# H-brigde_connector.net
KiCad netlist of a schematic drawn in Altium Designer
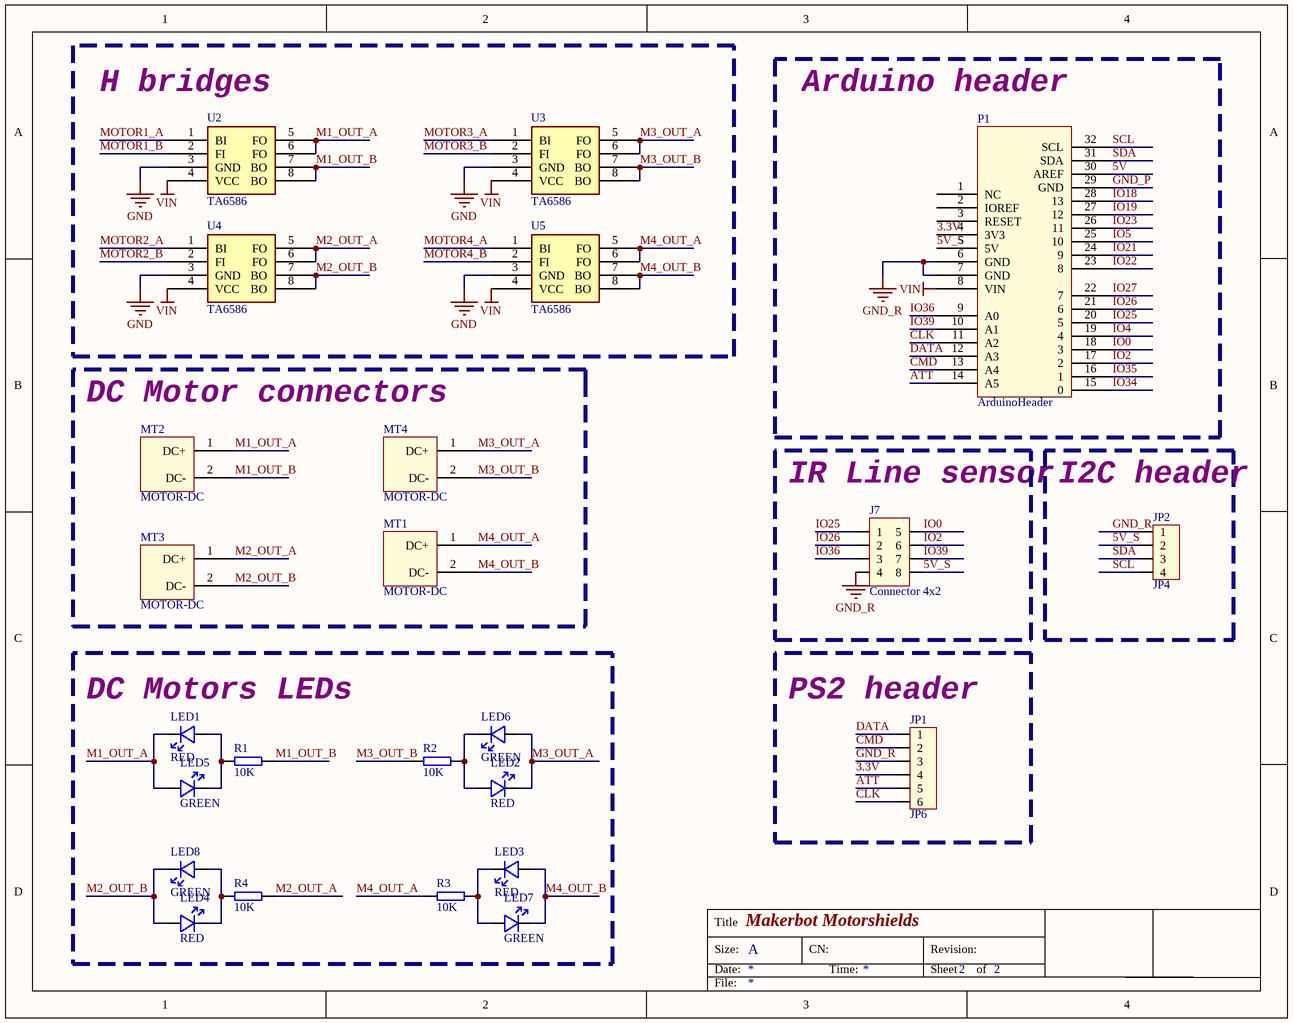
[diagram p0: H-brigde_connector.SchDoc]

(export (version "E")
  (design (tool "Eeschema 10.0.6"))
  (components
    (comp (ref "J7")
      (value "Connector 4x2")
      (footprint "JP4x2")
      (libsource (lib "My library altium") (part "JP4x2"))
    )
    (comp (ref "JP1")
      (value "JP6")
      (footprint "CON6")
      (description "Connector 6")
      (libsource (lib "My Library") (part "Con6"))
    )
    (comp (ref "JP2")
      (value "JP4")
      (footprint "CONN-TH_XH2.54-4AW")
      (description "Connector 4")
      (libsource (lib "My Library") (part "Con4"))
    )
    (comp (ref "LED1")
      (value "RED")
      (footprint "SMT0603P")
      (description "LED SM 0603 RED 1V95 FWD VOLTAGE")
      (libsource (lib "electronpowered") (part "LNJ237W82RA"))
    )
    (comp (ref "LED2")
      (value "RED")
      (footprint "SMT0603P")
      (description "LED SM 0603 RED 1V95 FWD VOLTAGE")
      (libsource (lib "electronpowered") (part "LNJ237W82RA"))
    )
    (comp (ref "LED3")
      (value "RED")
      (footprint "SMT0603P")
      (description "LED SM 0603 RED 1V95 FWD VOLTAGE")
      (libsource (lib "electronpowered") (part "LNJ237W82RA"))
    )
    (comp (ref "LED4")
      (value "RED")
      (footprint "SMT0603P")
      (description "LED SM 0603 RED 1V95 FWD VOLTAGE")
      (libsource (lib "electronpowered") (part "LNJ237W82RA"))
    )
    (comp (ref "LED5")
      (value "GREEN")
      (footprint "SMT0603P")
      (description "LED SM 0603 GREEN 1V95 FWD VOLTAGE")
      (libsource (lib "electronpowered") (part "LNJ337W83RA"))
    )
    (comp (ref "LED6")
      (value "GREEN")
      (footprint "SMT0603P")
      (description "LED SM 0603 GREEN 1V95 FWD VOLTAGE")
      (libsource (lib "electronpowered") (part "LNJ337W83RA"))
    )
    (comp (ref "LED7")
      (value "GREEN")
      (footprint "SMT0603P")
      (description "LED SM 0603 GREEN 1V95 FWD VOLTAGE")
      (libsource (lib "electronpowered") (part "LNJ337W83RA"))
    )
    (comp (ref "LED8")
      (value "GREEN")
      (footprint "SMT0603P")
      (description "LED SM 0603 GREEN 1V95 FWD VOLTAGE")
      (libsource (lib "electronpowered") (part "LNJ337W83RA"))
    )
    (comp (ref "MT1")
      (value "MOTOR-DC")
      (footprint "CON2-5.08DC")
      (libsource (lib "RASHBERRY_EXTERN") (part "MOTOR-DC"))
    )
    (comp (ref "MT2")
      (value "MOTOR-DC")
      (footprint "CON2-5.08DC")
      (libsource (lib "RASHBERRY_EXTERN") (part "MOTOR-DC"))
    )
    (comp (ref "MT3")
      (value "MOTOR-DC")
      (footprint "CON2-5.08DC")
      (libsource (lib "RASHBERRY_EXTERN") (part "MOTOR-DC"))
    )
    (comp (ref "MT4")
      (value "MOTOR-DC")
      (footprint "CON2-5.08DC")
      (libsource (lib "RASHBERRY_EXTERN") (part "MOTOR-DC"))
    )
    (comp (ref "P1")
      (value "ArduinoHeader")
      (footprint "ArduinoClone2")
      (libsource (lib "electronpowered") (part "ArduinoHeader"))
    )
    (comp (ref "R1")
      (value "10K")
      (footprint "SMT0603")
      (description "RES SM 0603 10K")
      (fields (field (name "Comment") "Resistor"))
      (libsource (lib "electronpowered") (part "RES-SM-0603-10K"))
    )
    (comp (ref "R2")
      (value "10K")
      (footprint "SMT0603")
      (description "RES SM 0603 10K")
      (fields (field (name "Comment") "Resistor"))
      (libsource (lib "electronpowered") (part "RES-SM-0603-10K"))
    )
    (comp (ref "R3")
      (value "10K")
      (footprint "SMT0603")
      (description "RES SM 0603 10K")
      (fields (field (name "Comment") "Resistor"))
      (libsource (lib "electronpowered") (part "RES-SM-0603-10K"))
    )
    (comp (ref "R4")
      (value "10K")
      (footprint "SMT0603")
      (description "RES SM 0603 10K")
      (fields (field (name "Comment") "Resistor"))
      (libsource (lib "electronpowered") (part "RES-SM-0603-10K"))
    )
    (comp (ref "U2")
      (value "TA6586")
      (footprint "DIP.100/8/W.300/L.400")
      (libsource (lib "TA6586") (part "TA6586"))
    )
    (comp (ref "U3")
      (value "TA6586")
      (footprint "DIP.100/8/W.300/L.400")
      (libsource (lib "TA6586") (part "TA6586"))
    )
    (comp (ref "U4")
      (value "TA6586")
      (footprint "DIP.100/8/W.300/L.400")
      (libsource (lib "TA6586") (part "TA6586"))
    )
    (comp (ref "U5")
      (value "TA6586")
      (footprint "DIP.100/8/W.300/L.400")
      (libsource (lib "TA6586") (part "TA6586"))
    )
  )
  (nets
    (net (code "1") (name "/3.3V") (class "Default")
      (node (ref "JP1") (pin "4") (pinfunction "4_4") (pintype "passive"))
      (node (ref "P1") (pin "4") (pinfunction "3V3_4") (pintype "passive"))
    )
    (net (code "2") (name "/5V") (class "Default")
      (node (ref "P1") (pin "30") (pinfunction "AREF_30") (pintype "passive"))
    )
    (net (code "3") (name "/5V_S") (class "Default")
      (node (ref "J7") (pin "8") (pinfunction "8_8") (pintype "passive"))
      (node (ref "JP2") (pin "2") (pinfunction "2_2") (pintype "passive"))
      (node (ref "P1") (pin "5") (pinfunction "5V_5") (pintype "passive"))
    )
    (net (code "4") (name "/ATT") (class "Default")
      (node (ref "JP1") (pin "5") (pinfunction "5_5") (pintype "passive"))
      (node (ref "P1") (pin "14") (pinfunction "A5_14") (pintype "passive"))
    )
    (net (code "5") (name "/CLK") (class "Default")
      (node (ref "JP1") (pin "6") (pinfunction "6_6") (pintype "passive"))
      (node (ref "P1") (pin "11") (pinfunction "A2_11") (pintype "passive"))
    )
    (net (code "6") (name "/CMD") (class "Default")
      (node (ref "JP1") (pin "2") (pinfunction "2_2") (pintype "passive"))
      (node (ref "P1") (pin "13") (pinfunction "A4_13") (pintype "passive"))
    )
    (net (code "7") (name "/DATA") (class "Default")
      (node (ref "JP1") (pin "1") (pinfunction "1_1") (pintype "passive"))
      (node (ref "P1") (pin "12") (pinfunction "A3_12") (pintype "passive"))
    )
    (net (code "8") (name "/GND_P") (class "Default")
      (node (ref "P1") (pin "29") (pinfunction "GND_29") (pintype "passive"))
    )
    (net (code "9") (name "/IO0") (class "Default")
      (node (ref "J7") (pin "5") (pinfunction "5_5") (pintype "passive"))
      (node (ref "P1") (pin "18") (pinfunction "3_18") (pintype "passive"))
    )
    (net (code "10") (name "/IO2") (class "Default")
      (node (ref "J7") (pin "6") (pinfunction "6_6") (pintype "passive"))
      (node (ref "P1") (pin "17") (pinfunction "2_17") (pintype "passive"))
    )
    (net (code "11") (name "/IO4") (class "Default")
      (node (ref "P1") (pin "19") (pinfunction "4_19") (pintype "passive"))
    )
    (net (code "12") (name "/IO5") (class "Default")
      (node (ref "P1") (pin "25") (pinfunction "10_25") (pintype "passive"))
    )
    (net (code "13") (name "/IO18") (class "Default")
      (node (ref "P1") (pin "28") (pinfunction "13_28") (pintype "passive"))
    )
    (net (code "14") (name "/IO19") (class "Default")
      (node (ref "P1") (pin "27") (pinfunction "12_27") (pintype "passive"))
    )
    (net (code "15") (name "/IO21") (class "Default")
      (node (ref "P1") (pin "24") (pinfunction "9_24") (pintype "passive"))
    )
    (net (code "16") (name "/IO22") (class "Default")
      (node (ref "P1") (pin "23") (pinfunction "8_23") (pintype "passive"))
    )
    (net (code "17") (name "/IO23") (class "Default")
      (node (ref "P1") (pin "26") (pinfunction "11_26") (pintype "passive"))
    )
    (net (code "18") (name "/IO25") (class "Default")
      (node (ref "J7") (pin "1") (pinfunction "1_1") (pintype "passive"))
      (node (ref "P1") (pin "20") (pinfunction "5_20") (pintype "passive"))
    )
    (net (code "19") (name "/IO26") (class "Default")
      (node (ref "J7") (pin "2") (pinfunction "2_2") (pintype "passive"))
      (node (ref "P1") (pin "21") (pinfunction "6_21") (pintype "passive"))
    )
    (net (code "20") (name "/IO27") (class "Default")
      (node (ref "P1") (pin "22") (pinfunction "7_22") (pintype "passive"))
    )
    (net (code "21") (name "/IO34") (class "Default")
      (node (ref "P1") (pin "15") (pinfunction "0_15") (pintype "passive"))
    )
    (net (code "22") (name "/IO35") (class "Default")
      (node (ref "P1") (pin "16") (pinfunction "1_16") (pintype "passive"))
    )
    (net (code "23") (name "/IO36") (class "Default")
      (node (ref "J7") (pin "3") (pinfunction "3_3") (pintype "passive"))
      (node (ref "P1") (pin "9") (pinfunction "A0_9") (pintype "passive"))
    )
    (net (code "24") (name "/IO39") (class "Default")
      (node (ref "J7") (pin "7") (pinfunction "7_7") (pintype "passive"))
      (node (ref "P1") (pin "10") (pinfunction "A1_10") (pintype "passive"))
    )
    (net (code "25") (name "/M1_OUT_A") (class "Default")
      (node (ref "LED1") (pin "2") (pinfunction "2_2") (pintype "passive"))
      (node (ref "LED5") (pin "1") (pinfunction "1_1") (pintype "passive"))
      (node (ref "MT2") (pin "1") (pinfunction "DC+_1") (pintype "passive"))
      (node (ref "U2") (pin "5") (pinfunction "FO_5") (pintype "passive"))
      (node (ref "U2") (pin "6") (pinfunction "FO_6") (pintype "passive"))
    )
    (net (code "26") (name "/M1_OUT_B") (class "Default")
      (node (ref "MT2") (pin "2") (pinfunction "DC-_2") (pintype "passive"))
      (node (ref "R1") (pin "2") (pinfunction "2_2") (pintype "passive"))
      (node (ref "U2") (pin "7") (pinfunction "BO_7") (pintype "passive"))
      (node (ref "U2") (pin "8") (pinfunction "BO_8") (pintype "passive"))
    )
    (net (code "27") (name "/M2_OUT_A") (class "Default")
      (node (ref "MT3") (pin "1") (pinfunction "DC+_1") (pintype "passive"))
      (node (ref "R4") (pin "1") (pinfunction "1_1") (pintype "passive"))
      (node (ref "U4") (pin "5") (pinfunction "FO_5") (pintype "passive"))
      (node (ref "U4") (pin "6") (pinfunction "FO_6") (pintype "passive"))
    )
    (net (code "28") (name "/M2_OUT_B") (class "Default")
      (node (ref "LED4") (pin "1") (pinfunction "1_1") (pintype "passive"))
      (node (ref "LED8") (pin "2") (pinfunction "2_2") (pintype "passive"))
      (node (ref "MT3") (pin "2") (pinfunction "DC-_2") (pintype "passive"))
      (node (ref "U4") (pin "7") (pinfunction "BO_7") (pintype "passive"))
      (node (ref "U4") (pin "8") (pinfunction "BO_8") (pintype "passive"))
    )
    (net (code "29") (name "/M3_OUT_A") (class "Default")
      (node (ref "LED2") (pin "2") (pinfunction "2_2") (pintype "passive"))
      (node (ref "LED6") (pin "1") (pinfunction "1_1") (pintype "passive"))
      (node (ref "MT4") (pin "1") (pinfunction "DC+_1") (pintype "passive"))
      (node (ref "U3") (pin "5") (pinfunction "FO_5") (pintype "passive"))
      (node (ref "U3") (pin "6") (pinfunction "FO_6") (pintype "passive"))
    )
    (net (code "30") (name "/M3_OUT_B") (class "Default")
      (node (ref "MT4") (pin "2") (pinfunction "DC-_2") (pintype "passive"))
      (node (ref "R2") (pin "2") (pinfunction "2_2") (pintype "passive"))
      (node (ref "U3") (pin "7") (pinfunction "BO_7") (pintype "passive"))
      (node (ref "U3") (pin "8") (pinfunction "BO_8") (pintype "passive"))
    )
    (net (code "31") (name "/M4_OUT_A") (class "Default")
      (node (ref "MT1") (pin "1") (pinfunction "DC+_1") (pintype "passive"))
      (node (ref "R3") (pin "1") (pinfunction "1_1") (pintype "passive"))
      (node (ref "U5") (pin "5") (pinfunction "FO_5") (pintype "passive"))
      (node (ref "U5") (pin "6") (pinfunction "FO_6") (pintype "passive"))
    )
    (net (code "32") (name "/M4_OUT_B") (class "Default")
      (node (ref "LED3") (pin "1") (pinfunction "1_1") (pintype "passive"))
      (node (ref "LED7") (pin "2") (pinfunction "2_2") (pintype "passive"))
      (node (ref "MT1") (pin "2") (pinfunction "DC-_2") (pintype "passive"))
      (node (ref "U5") (pin "7") (pinfunction "BO_7") (pintype "passive"))
      (node (ref "U5") (pin "8") (pinfunction "BO_8") (pintype "passive"))
    )
    (net (code "33") (name "/MOTOR1_A") (class "Default")
      (node (ref "U2") (pin "1") (pinfunction "BI_1") (pintype "passive"))
    )
    (net (code "34") (name "/MOTOR1_B") (class "Default")
      (node (ref "U2") (pin "2") (pinfunction "FI_2") (pintype "passive"))
    )
    (net (code "35") (name "/MOTOR2_A") (class "Default")
      (node (ref "U4") (pin "1") (pinfunction "BI_1") (pintype "passive"))
    )
    (net (code "36") (name "/MOTOR2_B") (class "Default")
      (node (ref "U4") (pin "2") (pinfunction "FI_2") (pintype "passive"))
    )
    (net (code "37") (name "/MOTOR3_A") (class "Default")
      (node (ref "U3") (pin "1") (pinfunction "BI_1") (pintype "passive"))
    )
    (net (code "38") (name "/MOTOR3_B") (class "Default")
      (node (ref "U3") (pin "2") (pinfunction "FI_2") (pintype "passive"))
    )
    (net (code "39") (name "/MOTOR4_A") (class "Default")
      (node (ref "U5") (pin "1") (pinfunction "BI_1") (pintype "passive"))
    )
    (net (code "40") (name "/MOTOR4_B") (class "Default")
      (node (ref "U5") (pin "2") (pinfunction "FI_2") (pintype "passive"))
    )
    (net (code "41") (name "/SCL") (class "Default")
      (node (ref "JP2") (pin "4") (pinfunction "4_4") (pintype "passive"))
      (node (ref "P1") (pin "32") (pinfunction "SCL_32") (pintype "passive"))
    )
    (net (code "42") (name "/SDA") (class "Default")
      (node (ref "JP2") (pin "3") (pinfunction "3_3") (pintype "passive"))
      (node (ref "P1") (pin "31") (pinfunction "SDA_31") (pintype "passive"))
    )
    (net (code "43") (name "GND") (class "Default")
      (node (ref "U2") (pin "3") (pinfunction "GND_3") (pintype "passive"))
      (node (ref "U3") (pin "3") (pinfunction "GND_3") (pintype "passive"))
      (node (ref "U4") (pin "3") (pinfunction "GND_3") (pintype "passive"))
      (node (ref "U5") (pin "3") (pinfunction "GND_3") (pintype "passive"))
    )
    (net (code "44") (name "GND_R") (class "Default")
      (node (ref "J7") (pin "4") (pinfunction "4_4") (pintype "passive"))
      (node (ref "JP1") (pin "3") (pinfunction "3_3") (pintype "passive"))
      (node (ref "JP2") (pin "1") (pinfunction "1_1") (pintype "passive"))
      (node (ref "P1") (pin "6") (pinfunction "GND_6") (pintype "passive"))
      (node (ref "P1") (pin "7") (pinfunction "GND_7") (pintype "passive"))
    )
    (net (code "45") (name "Net-(LED1-Pad1)") (class "Default")
      (node (ref "LED1") (pin "1") (pinfunction "1_1") (pintype "passive"))
      (node (ref "LED5") (pin "2") (pinfunction "2_2") (pintype "passive"))
      (node (ref "R1") (pin "1") (pinfunction "1_1") (pintype "passive"))
    )
    (net (code "46") (name "Net-(LED2-Pad1)") (class "Default")
      (node (ref "LED2") (pin "1") (pinfunction "1_1") (pintype "passive"))
      (node (ref "LED6") (pin "2") (pinfunction "2_2") (pintype "passive"))
      (node (ref "R2") (pin "1") (pinfunction "1_1") (pintype "passive"))
    )
    (net (code "47") (name "Net-(LED3-Pad2)") (class "Default")
      (node (ref "LED3") (pin "2") (pinfunction "2_2") (pintype "passive"))
      (node (ref "LED7") (pin "1") (pinfunction "1_1") (pintype "passive"))
      (node (ref "R3") (pin "2") (pinfunction "2_2") (pintype "passive"))
    )
    (net (code "48") (name "Net-(LED4-Pad2)") (class "Default")
      (node (ref "LED4") (pin "2") (pinfunction "2_2") (pintype "passive"))
      (node (ref "LED8") (pin "1") (pinfunction "1_1") (pintype "passive"))
      (node (ref "R4") (pin "2") (pinfunction "2_2") (pintype "passive"))
    )
    (net (code "49") (name "VIN") (class "Default")
      (node (ref "P1") (pin "8") (pinfunction "VIN_8") (pintype "passive"))
      (node (ref "U2") (pin "4") (pinfunction "VCC_4") (pintype "passive"))
      (node (ref "U3") (pin "4") (pinfunction "VCC_4") (pintype "passive"))
      (node (ref "U4") (pin "4") (pinfunction "VCC_4") (pintype "passive"))
      (node (ref "U5") (pin "4") (pinfunction "VCC_4") (pintype "passive"))
    )
    (net (code "50") (name "unconnected-(P1-IOREF-Pad2)") (class "Default")
      (node (ref "P1") (pin "2") (pinfunction "IOREF_2") (pintype "passive"))
    )
    (net (code "51") (name "unconnected-(P1-NC-Pad1)") (class "Default")
      (node (ref "P1") (pin "1") (pinfunction "NC_1") (pintype "passive"))
    )
    (net (code "52") (name "unconnected-(P1-RESET-Pad3)") (class "Default")
      (node (ref "P1") (pin "3") (pinfunction "RESET_3") (pintype "passive"))
    )
  )
)
